# Sensor_Box_Simple_IO.net
KiCad netlist of a schematic drawn in Altium Designer
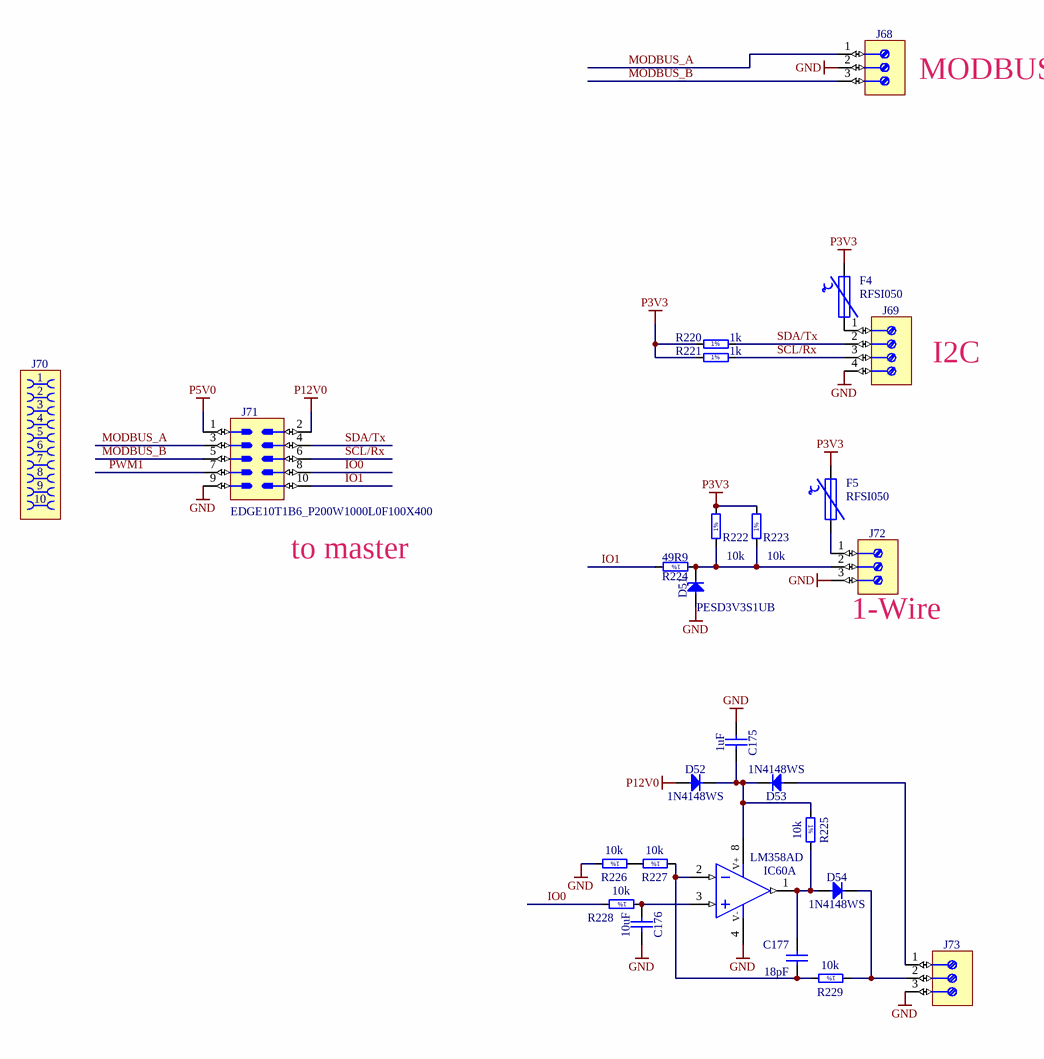
[diagram p0: Sensor_Box_Simple_IO.SchDoc]

(export (version "E")
  (design (tool "Eeschema 10.0.6"))
  (components
    (comp (ref "C175")
      (value "1uF")
      (footprint "CAPC1005X55N")
      (description "Non-polarised capacitor")
      (fields
        (field (name "PART NUMBER") "CC0402_1UF_16V_10%_X5R")
        (field (name "VOLTAGE") "16V")
        (field (name "AUTHOR") "CERN DEM JLC")
      )
      (libsource (lib "Capacitors") (part "Capacitor - non polarized"))
    )
    (comp (ref "C176")
      (value "10uF")
      (footprint "CAPC2012X135N")
      (description "Non-polarised capacitor")
      (fields
        (field (name "PART NUMBER") "CC0805_10UF_16V_10%_X5R")
        (field (name "VOLTAGE") "16V")
        (field (name "AUTHOR") "CERN DEM JLC")
      )
      (libsource (lib "Capacitors") (part "Capacitor - non polarized"))
    )
    (comp (ref "C177")
      (value "18pF")
      (footprint "CAPC1005X55N")
      (description "Non-polarised capacitor")
      (fields
        (field (name "PART NUMBER") "CC0402_18PF_50V_5%_C0G")
        (field (name "VOLTAGE") "50V")
        (field (name "AUTHOR") "CERN DEM JLC")
      )
      (libsource (lib "Capacitors") (part "Capacitor - non polarized"))
    )
    (comp (ref "D51")
      (value "PESD3V3S1UB")
      (footprint "SODFL1608X65N")
      (description "ESD protection diode")
      (fields
        (field (name "VOLTAGE") "3V3")
        (field (name "POWER") "330W")
        (field (name "AUTHOR") "CERN DEM JLC")
      )
      (libsource (lib "ICs And Semiconductors") (part "Diode ESD"))
    )
    (comp (ref "D52")
      (value "1N4148WS")
      (footprint "SODFL2512X100N")
      (description "Diode")
      (fields
        (field (name "VOLTAGE") "75V")
        (field (name "POWER") "150mA")
        (field (name "AUTHOR") "CERN DEM JLC")
      )
      (libsource (lib "ICs And Semiconductors") (part "Diode"))
    )
    (comp (ref "D53")
      (value "1N4148WS")
      (footprint "SODFL2512X100N")
      (description "Diode")
      (fields
        (field (name "VOLTAGE") "75V")
        (field (name "POWER") "150mA")
        (field (name "AUTHOR") "CERN DEM JLC")
      )
      (libsource (lib "ICs And Semiconductors") (part "Diode"))
    )
    (comp (ref "D54")
      (value "1N4148WS")
      (footprint "SODFL2512X100N")
      (description "Diode")
      (fields
        (field (name "VOLTAGE") "75V")
        (field (name "POWER") "150mA")
        (field (name "AUTHOR") "CERN DEM JLC")
      )
      (libsource (lib "ICs And Semiconductors") (part "Diode"))
    )
    (comp (ref "F4")
      (value "RFSI050")
      (footprint "0805R")
      (description "50mA polymer FUSE")
      (libsource (lib "LIBRARY_SCH") (part "F_PTC_0.05A"))
    )
    (comp (ref "F5")
      (value "RFSI050")
      (footprint "0805R")
      (description "50mA polymer FUSE")
      (libsource (lib "LIBRARY_SCH") (part "F_PTC_0.05A"))
    )
    (comp (ref "IC60")
      (value "LM358AD")
      (footprint "SOIC127P600X175-8N")
      (description "Dual Operational Amplifier")
      (fields (field (name "MANUFACTURER") "TEXAS INSTRUMENTS") (field (name "AUTHOR") "CERN DEM JLC"))
      (libsource (lib "ICs And Semiconductors") (part "Operational Amplifier x2 Type1"))
    )
    (comp (ref "J68")
      (value "~")
      (footprint "PHOENIX_1725669")
      (description "Terminal Block, 3 Positions, Screw Connection")
      (fields
        (field (name "PART NUMBER") "PHOENIX_1725669")
        (field (name "MANUFACTURER") "PHOENIX CONTACT")
        (field (name "AUTHOR") "CERN DEM JMW")
      )
      (libsource (lib "Connectors") (part "Terminal Block_3 Positions_Screw Connection"))
    )
    (comp (ref "J69")
      (value "~")
      (footprint "PHOENIX_1725672")
      (description "Terminal Block, 4 Positions, Screw Connection")
      (fields
        (field (name "PART NUMBER") "PHOENIX_1725672")
        (field (name "MANUFACTURER") "PHOENIX CONTACT")
        (field (name "AUTHOR") "CERN DEM JMW")
      )
      (libsource (lib "Connectors") (part "Terminal Block_4 Positions_Screw Connection"))
    )
    (comp (ref "J70")
      (value "~")
      (footprint "AVX_00 9159 010 061 916")
      (description "Open Ended Card Edge Connector, 9159 Series")
      (fields
        (field (name "PART NUMBER") "AVX_00 9159 010 061 916")
        (field (name "MANUFACTURER") "AVX")
        (field (name "AUTHOR") "CERN DEM MR")
      )
      (libsource (lib "Connectors") (part "AVX_00 9159 010 061 916"))
    )
    (comp (ref "J71")
      (value "~")
      (footprint "EDGE10T1B6_P200W1000L0F100X400")
      (description "PCB Edge Connector 10 (2x5)")
      (fields
        (field (name "PART NUMBER") "EDGE10T1B6_P200W1000L0F100X400")
        (field (name "AUTHOR") "CERN DEM MR")
      )
      (libsource (lib "Connectors") (part "PCB Edge Connector 10 (2x5)"))
    )
    (comp (ref "J72")
      (value "~")
      (footprint "PHOENIX_1725669")
      (description "Terminal Block, 3 Positions, Screw Connection")
      (fields
        (field (name "PART NUMBER") "PHOENIX_1725669")
        (field (name "MANUFACTURER") "PHOENIX CONTACT")
        (field (name "AUTHOR") "CERN DEM JMW")
      )
      (libsource (lib "Connectors") (part "Terminal Block_3 Positions_Screw Connection"))
    )
    (comp (ref "J73")
      (value "~")
      (footprint "PHOENIX_1725669")
      (description "Terminal Block, 3 Positions, Screw Connection")
      (fields
        (field (name "PART NUMBER") "PHOENIX_1725669")
        (field (name "MANUFACTURER") "PHOENIX CONTACT")
        (field (name "AUTHOR") "CERN DEM JMW")
      )
      (libsource (lib "Connectors") (part "Terminal Block_3 Positions_Screw Connection"))
    )
    (comp (ref "R220")
      (value "1k")
      (footprint "RESC1005X40N")
      (description "Resistor - 1%")
      (fields
        (field (name "PART NUMBER") "R0402_1K_1%_0.0625W_100PPM")
        (field (name "POWER") "0.0625W")
        (field (name "AUTHOR") "CERN DEM JLC")
      )
      (libsource (lib "Resistors") (part "Resistor - 1%"))
    )
    (comp (ref "R221")
      (value "1k")
      (footprint "RESC1005X40N")
      (description "Resistor - 1%")
      (fields
        (field (name "PART NUMBER") "R0402_1K_1%_0.0625W_100PPM")
        (field (name "POWER") "0.0625W")
        (field (name "AUTHOR") "CERN DEM JLC")
      )
      (libsource (lib "Resistors") (part "Resistor - 1%"))
    )
    (comp (ref "R222")
      (value "10k")
      (footprint "RESC1005X40N")
      (description "Resistor - 1%")
      (fields
        (field (name "PART NUMBER") "R0402_10K_1%_0.0625W_100PPM")
        (field (name "POWER") "0.0625W")
        (field (name "AUTHOR") "CERN DEM JLC")
      )
      (libsource (lib "Resistors") (part "Resistor - 1%"))
    )
    (comp (ref "R223")
      (value "10k")
      (footprint "RESC1005X40N")
      (description "Resistor - 1%")
      (fields
        (field (name "PART NUMBER") "R0402_10K_1%_0.0625W_100PPM")
        (field (name "POWER") "0.0625W")
        (field (name "AUTHOR") "CERN DEM JLC")
      )
      (libsource (lib "Resistors") (part "Resistor - 1%"))
    )
    (comp (ref "R224")
      (value "49R9")
      (footprint "RESC1005X40N")
      (description "Resistor - 1%")
      (fields
        (field (name "PART NUMBER") "R0402_49R9_1%_0.0625W_100PPM")
        (field (name "POWER") "0.0625W")
        (field (name "AUTHOR") "CERN DEM JLC")
      )
      (libsource (lib "Resistors") (part "Resistor - 1%"))
    )
    (comp (ref "R225")
      (value "10k")
      (footprint "RESC1005X40N")
      (description "Resistor - 1%")
      (fields
        (field (name "PART NUMBER") "R0402_10K_1%_0.0625W_100PPM")
        (field (name "POWER") "0.0625W")
        (field (name "AUTHOR") "CERN DEM JLC")
      )
      (libsource (lib "Resistors") (part "Resistor - 1%"))
    )
    (comp (ref "R226")
      (value "10k")
      (footprint "RESC1005X40N")
      (description "Resistor - 1%")
      (fields
        (field (name "PART NUMBER") "R0402_10K_1%_0.0625W_100PPM")
        (field (name "POWER") "0.0625W")
        (field (name "AUTHOR") "CERN DEM JLC")
      )
      (libsource (lib "Resistors") (part "Resistor - 1%"))
    )
    (comp (ref "R227")
      (value "10k")
      (footprint "RESC1005X40N")
      (description "Resistor - 1%")
      (fields
        (field (name "PART NUMBER") "R0402_10K_1%_0.0625W_100PPM")
        (field (name "POWER") "0.0625W")
        (field (name "AUTHOR") "CERN DEM JLC")
      )
      (libsource (lib "Resistors") (part "Resistor - 1%"))
    )
    (comp (ref "R228")
      (value "10k")
      (footprint "RESC1005X40N")
      (description "Resistor - 1%")
      (fields
        (field (name "PART NUMBER") "R0402_10K_1%_0.0625W_100PPM")
        (field (name "POWER") "0.0625W")
        (field (name "AUTHOR") "CERN DEM JLC")
      )
      (libsource (lib "Resistors") (part "Resistor - 1%"))
    )
    (comp (ref "R229")
      (value "10k")
      (footprint "RESC1005X40N")
      (description "Resistor - 1%")
      (fields
        (field (name "PART NUMBER") "R0402_10K_1%_0.0625W_100PPM")
        (field (name "POWER") "0.0625W")
        (field (name "AUTHOR") "CERN DEM JLC")
      )
      (libsource (lib "Resistors") (part "Resistor - 1%"))
    )
  )
  (nets
    (net (code "1") (name "/IO0") (class "Default")
      (node (ref "J71") (pin "8") (pinfunction "8_8") (pintype "bidirectional"))
      (node (ref "R228") (pin "2") (pinfunction "2_2") (pintype "passive"))
    )
    (net (code "2") (name "/IO1") (class "Default")
      (node (ref "J71") (pin "10") (pinfunction "10_10") (pintype "bidirectional"))
      (node (ref "R224") (pin "2") (pinfunction "2_2") (pintype "passive"))
    )
    (net (code "3") (name "/MODBUS_A") (class "Default")
      (node (ref "J68") (pin "1") (pinfunction "1_1") (pintype "bidirectional"))
      (node (ref "J71") (pin "3") (pinfunction "3_3") (pintype "bidirectional"))
    )
    (net (code "4") (name "/MODBUS_B") (class "Default")
      (node (ref "J68") (pin "3") (pinfunction "3_3") (pintype "bidirectional"))
      (node (ref "J71") (pin "5") (pinfunction "5_5") (pintype "bidirectional"))
    )
    (net (code "5") (name "/PWM1") (class "Default")
      (node (ref "J71") (pin "7") (pinfunction "7_7") (pintype "bidirectional"))
    )
    (net (code "6") (name "/SCL{slash}Rx") (class "Default")
      (node (ref "J69") (pin "3") (pinfunction "3_3") (pintype "bidirectional"))
      (node (ref "J71") (pin "6") (pinfunction "6_6") (pintype "bidirectional"))
      (node (ref "R221") (pin "2") (pinfunction "2_2") (pintype "passive"))
    )
    (net (code "7") (name "/SDA{slash}Tx") (class "Default")
      (node (ref "J69") (pin "2") (pinfunction "2_2") (pintype "bidirectional"))
      (node (ref "J71") (pin "4") (pinfunction "4_4") (pintype "bidirectional"))
      (node (ref "R220") (pin "2") (pinfunction "2_2") (pintype "passive"))
    )
    (net (code "8") (name "GND") (class "Default")
      (node (ref "C175") (pin "1") (pinfunction "1_1") (pintype "passive"))
      (node (ref "C176") (pin "2") (pinfunction "2_2") (pintype "passive"))
      (node (ref "D51") (pin "2") (pinfunction "A_2") (pintype "passive"))
      (node (ref "IC60") (pin "4") (pinfunction "V-_4") (pintype "power_in"))
      (node (ref "J68") (pin "2") (pinfunction "2_2") (pintype "bidirectional"))
      (node (ref "J69") (pin "4") (pinfunction "4_4") (pintype "bidirectional"))
      (node (ref "J71") (pin "9") (pinfunction "9_9") (pintype "bidirectional"))
      (node (ref "J72") (pin "3") (pinfunction "3_3") (pintype "bidirectional"))
      (node (ref "J73") (pin "3") (pinfunction "3_3") (pintype "bidirectional"))
      (node (ref "R226") (pin "2") (pinfunction "2_2") (pintype "passive"))
    )
    (net (code "9") (name "Net-(D51-C)") (class "Default")
      (node (ref "D51") (pin "1") (pinfunction "C_1") (pintype "passive"))
      (node (ref "J72") (pin "2") (pinfunction "2_2") (pintype "bidirectional"))
      (node (ref "R222") (pin "1") (pinfunction "1_1") (pintype "passive"))
      (node (ref "R223") (pin "1") (pinfunction "1_1") (pintype "passive"))
      (node (ref "R224") (pin "1") (pinfunction "1_1") (pintype "passive"))
    )
    (net (code "10") (name "Net-(D52-C)") (class "Default")
      (node (ref "C175") (pin "2") (pinfunction "2_2") (pintype "passive"))
      (node (ref "D52") (pin "1") (pinfunction "C_1") (pintype "passive"))
      (node (ref "D53") (pin "1") (pinfunction "C_1") (pintype "passive"))
      (node (ref "IC60") (pin "8") (pinfunction "V+_8") (pintype "power_in"))
      (node (ref "R225") (pin "1") (pinfunction "1_1") (pintype "passive"))
    )
    (net (code "11") (name "Net-(D53-A)") (class "Default")
      (node (ref "D53") (pin "2") (pinfunction "A_2") (pintype "passive"))
      (node (ref "J73") (pin "1") (pinfunction "1_1") (pintype "bidirectional"))
    )
    (net (code "12") (name "Net-(D54-A)") (class "Default")
      (node (ref "C177") (pin "1") (pinfunction "1_1") (pintype "passive"))
      (node (ref "D54") (pin "2") (pinfunction "A_2") (pintype "passive"))
      (node (ref "IC60") (pin "1") (pinfunction "OUT_1") (pintype "output"))
      (node (ref "R225") (pin "2") (pinfunction "2_2") (pintype "passive"))
    )
    (net (code "13") (name "Net-(D54-C)") (class "Default")
      (node (ref "D54") (pin "1") (pinfunction "C_1") (pintype "passive"))
      (node (ref "J73") (pin "2") (pinfunction "2_2") (pintype "bidirectional"))
      (node (ref "R229") (pin "1") (pinfunction "1_1") (pintype "passive"))
    )
    (net (code "14") (name "Net-(F4-Pad1)") (class "Default")
      (node (ref "F4") (pin "1") (pinfunction "1_1") (pintype "passive"))
      (node (ref "J69") (pin "1") (pinfunction "1_1") (pintype "bidirectional"))
    )
    (net (code "15") (name "Net-(F5-Pad1)") (class "Default")
      (node (ref "F5") (pin "1") (pinfunction "1_1") (pintype "passive"))
      (node (ref "J72") (pin "1") (pinfunction "1_1") (pintype "bidirectional"))
    )
    (net (code "16") (name "Net-(IC60A-IN+)") (class "Default")
      (node (ref "C176") (pin "1") (pinfunction "1_1") (pintype "passive"))
      (node (ref "IC60") (pin "3") (pinfunction "IN+_3") (pintype "input"))
      (node (ref "R228") (pin "1") (pinfunction "1_1") (pintype "passive"))
    )
    (net (code "17") (name "Net-(IC60A-IN-)") (class "Default")
      (node (ref "C177") (pin "2") (pinfunction "2_2") (pintype "passive"))
      (node (ref "IC60") (pin "2") (pinfunction "IN-_2") (pintype "input"))
      (node (ref "R227") (pin "1") (pinfunction "1_1") (pintype "passive"))
      (node (ref "R229") (pin "2") (pinfunction "2_2") (pintype "passive"))
    )
    (net (code "18") (name "Net-(R226-Pad1)") (class "Default")
      (node (ref "R226") (pin "1") (pinfunction "1_1") (pintype "passive"))
      (node (ref "R227") (pin "2") (pinfunction "2_2") (pintype "passive"))
    )
    (net (code "19") (name "P3V3") (class "Default")
      (node (ref "F4") (pin "2") (pinfunction "2_2") (pintype "passive"))
      (node (ref "F5") (pin "2") (pinfunction "2_2") (pintype "passive"))
      (node (ref "R220") (pin "1") (pinfunction "1_1") (pintype "passive"))
      (node (ref "R221") (pin "1") (pinfunction "1_1") (pintype "passive"))
      (node (ref "R222") (pin "2") (pinfunction "2_2") (pintype "passive"))
      (node (ref "R223") (pin "2") (pinfunction "2_2") (pintype "passive"))
    )
    (net (code "20") (name "P5V0") (class "Default")
      (node (ref "J71") (pin "1") (pinfunction "1_1") (pintype "bidirectional"))
    )
    (net (code "21") (name "P12V0") (class "Default")
      (node (ref "D52") (pin "2") (pinfunction "A_2") (pintype "passive"))
      (node (ref "J71") (pin "2") (pinfunction "2_2") (pintype "bidirectional"))
    )
  )
)
